# 086-005.net
KiCad netlist of a schematic drawn in EAGLE
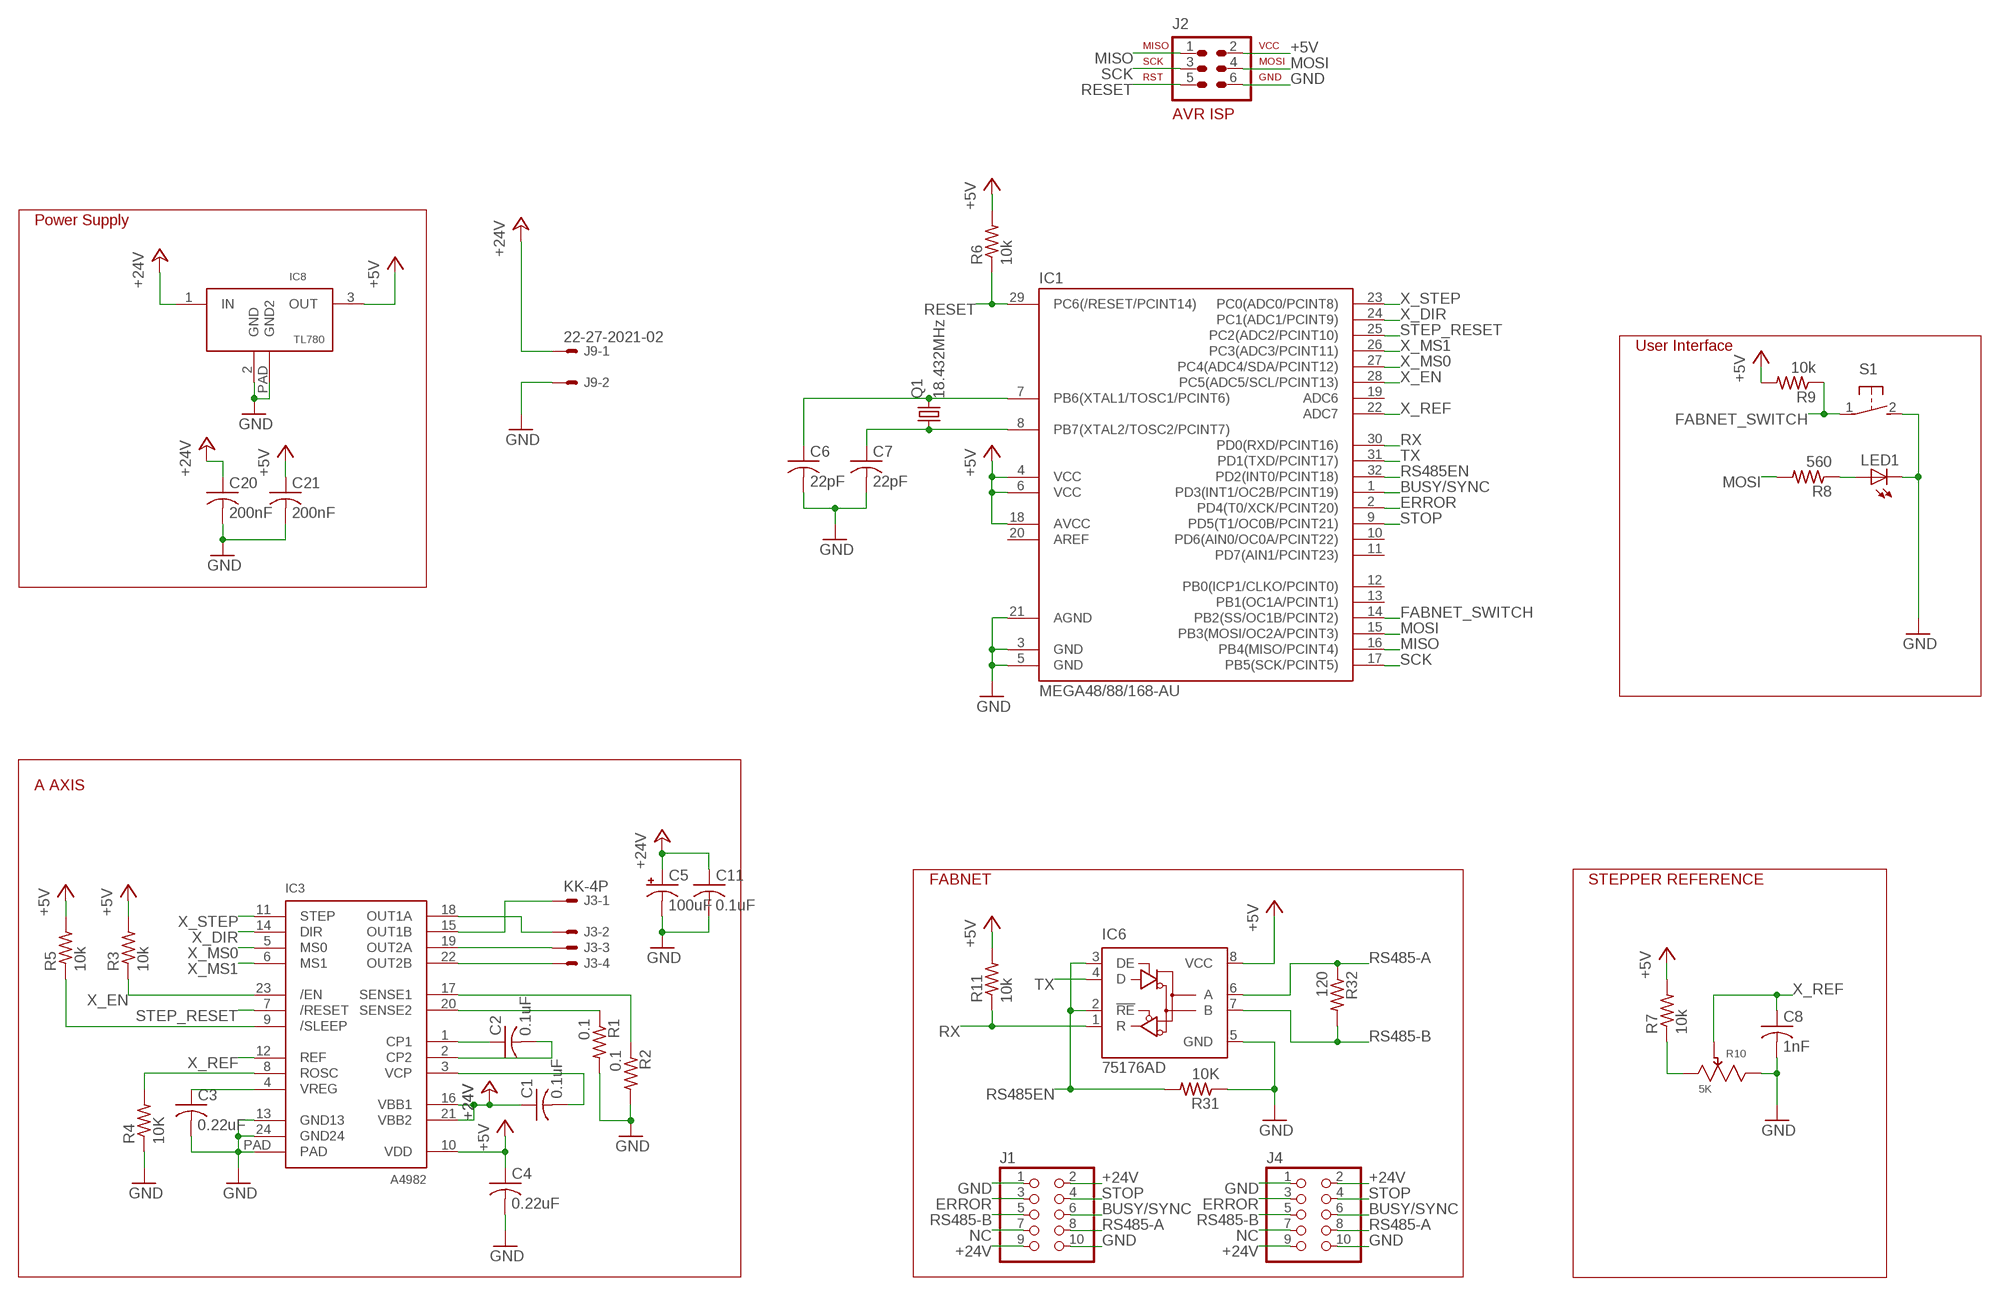
[diagram p0: schematic, sheet 1]

(export (version "E")
  (design (tool "Eeschema 10.0.6"))
  (components
    (comp (ref "C1")
      (value "0.1uF")
      (footprint "eagle-import:C0805")
      (libsource (lib "eagle-import") (part "C-USC0805"))
    )
    (comp (ref "C2")
      (value "0.1uF")
      (footprint "eagle-import:C0805")
      (libsource (lib "eagle-import") (part "C-USC0805"))
    )
    (comp (ref "C3")
      (value "0.22uF")
      (footprint "eagle-import:C0805")
      (libsource (lib "eagle-import") (part "C-USC0805"))
    )
    (comp (ref "C4")
      (value "0.22uF")
      (footprint "eagle-import:C0805")
      (libsource (lib "eagle-import") (part "C-USC0805"))
    )
    (comp (ref "C5")
      (value "100uF")
      (footprint "eagle-import:PANASONIC_D")
      (libsource (lib "eagle-import") (part "CPOL-USD"))
    )
    (comp (ref "C6")
      (value "22pF")
      (footprint "eagle-import:C0805")
      (libsource (lib "eagle-import") (part "C-USC0805"))
    )
    (comp (ref "C7")
      (value "22pF")
      (footprint "eagle-import:C0805")
      (libsource (lib "eagle-import") (part "C-USC0805"))
    )
    (comp (ref "C8")
      (value "1nF")
      (footprint "eagle-import:C0805")
      (libsource (lib "eagle-import") (part "C-USC0805"))
    )
    (comp (ref "C11")
      (value "0.1uF")
      (footprint "eagle-import:C0805")
      (libsource (lib "eagle-import") (part "C-USC0805"))
    )
    (comp (ref "C20")
      (value "200nF")
      (footprint "eagle-import:C0805")
      (libsource (lib "eagle-import") (part "C-USC0805"))
    )
    (comp (ref "C21")
      (value "200nF")
      (footprint "eagle-import:C0805")
      (libsource (lib "eagle-import") (part "C-USC0805"))
    )
    (comp (ref "IC1")
      (value "MEGA48/88/168-AU")
      (footprint "eagle-import:TQFP32-08")
      (libsource (lib "eagle-import") (part "MEGA48/88/168-AU"))
    )
    (comp (ref "IC3")
      (value "A4982")
      (footprint "eagle-import:TSSOP24_LP")
      (libsource (lib "eagle-import") (part "A4982"))
    )
    (comp (ref "IC6")
      (value "75176AD")
      (footprint "eagle-import:D_R-PDSO-G8")
      (libsource (lib "eagle-import") (part "75176AD"))
    )
    (comp (ref "IC8")
      (value "TL780_VREG")
      (footprint "eagle-import:D2PAK-3")
      (libsource (lib "eagle-import") (part "TL780_VREG"))
    )
    (comp (ref "J1")
      (value "PINHD-2X5")
      (footprint "eagle-import:2X05")
      (libsource (lib "eagle-import") (part "PINHD-2X5"))
    )
    (comp (ref "J2")
      (value "AVR-ISP-6VERT")
      (footprint "eagle-import:AVR-ISP-6")
      (libsource (lib "eagle-import") (part "AVR-ISP-6VERT"))
    )
    (comp (ref "J3")
      (value "KK-4P")
      (footprint "eagle-import:7395-04")
      (libsource (lib "eagle-import") (part "22-?-0405-7048"))
    )
    (comp (ref "J4")
      (value "PINHD-2X5")
      (footprint "eagle-import:2X05")
      (libsource (lib "eagle-import") (part "PINHD-2X5"))
    )
    (comp (ref "J9")
      (value "22-27-2021-02")
      (footprint "eagle-import:6410-02")
      (libsource (lib "eagle-import") (part "22-?-0227-2021"))
    )
    (comp (ref "LED1")
      (value "LEDCHIPLED_0603")
      (footprint "eagle-import:CHIPLED_0603")
      (libsource (lib "eagle-import") (part "LEDCHIPLED_0603"))
    )
    (comp (ref "Q1")
      (value "18.432MHz")
      (footprint "eagle-import:HC49UP")
      (fields (field (name "OC_FARNELL") "unknown") (field (name "OC_NEWARK") "unknown"))
      (libsource (lib "eagle-import") (part "CRYSTALHC49UP"))
    )
    (comp (ref "R1")
      (value "0.1")
      (footprint "eagle-import:R1206")
      (libsource (lib "eagle-import") (part "R-US_R1206"))
    )
    (comp (ref "R2")
      (value "0.1")
      (footprint "eagle-import:R1206")
      (libsource (lib "eagle-import") (part "R-US_R1206"))
    )
    (comp (ref "R3")
      (value "10k")
      (footprint "eagle-import:R0805")
      (libsource (lib "eagle-import") (part "R-US_R0805"))
    )
    (comp (ref "R4")
      (value "10K")
      (footprint "eagle-import:R0805")
      (libsource (lib "eagle-import") (part "R-US_R0805"))
    )
    (comp (ref "R5")
      (value "10k")
      (footprint "eagle-import:R0805")
      (libsource (lib "eagle-import") (part "R-US_R0805"))
    )
    (comp (ref "R6")
      (value "10k")
      (footprint "eagle-import:R0805")
      (libsource (lib "eagle-import") (part "R-US_R0805"))
    )
    (comp (ref "R7")
      (value "10k")
      (footprint "eagle-import:R0805")
      (libsource (lib "eagle-import") (part "R-US_R0805"))
    )
    (comp (ref "R8")
      (value "560")
      (footprint "eagle-import:R0805")
      (libsource (lib "eagle-import") (part "R-US_R0805"))
    )
    (comp (ref "R9")
      (value "10k")
      (footprint "eagle-import:R0805")
      (libsource (lib "eagle-import") (part "R-US_R0805"))
    )
    (comp (ref "R10")
      (value "5K")
      (footprint "eagle-import:BOURN_TRIM")
      (libsource (lib "eagle-import") (part "BOURN_POT"))
    )
    (comp (ref "R11")
      (value "10k")
      (footprint "eagle-import:R0805")
      (libsource (lib "eagle-import") (part "R-US_R0805"))
    )
    (comp (ref "R31")
      (value "10K")
      (footprint "eagle-import:R0805")
      (libsource (lib "eagle-import") (part "R-US_R0805"))
    )
    (comp (ref "R32")
      (value "120")
      (footprint "eagle-import:R0805")
      (libsource (lib "eagle-import") (part "R-US_R0805"))
    )
    (comp (ref "S1")
      (value "31-XX")
      (footprint "eagle-import:B3F-31XX")
      (fields (field (name "MPN") "B3F-3100"))
      (libsource (lib "eagle-import") (part "31-XX"))
    )
  )
  (nets
    (net (code "1") (name "+5V") (class "Default")
      (node (ref "C21") (pin "1") (pinfunction "1_1") (pintype "passive"))
      (node (ref "C4") (pin "1") (pinfunction "1_1") (pintype "passive"))
      (node (ref "IC1") (pin "18") (pinfunction "AVCC_18") (pintype "passive"))
      (node (ref "IC1") (pin "4") (pinfunction "VCC_4") (pintype "power_in"))
      (node (ref "IC1") (pin "6") (pinfunction "VCC_6") (pintype "power_in"))
      (node (ref "IC3") (pin "10") (pinfunction "VDD_10") (pintype "bidirectional"))
      (node (ref "IC6") (pin "8") (pinfunction "VCC_8") (pintype "power_in"))
      (node (ref "IC8") (pin "3") (pinfunction "OUT_3") (pintype "bidirectional"))
      (node (ref "J2") (pin "2") (pinfunction "2_2") (pintype "passive"))
      (node (ref "R11") (pin "2") (pinfunction "2_2") (pintype "passive"))
      (node (ref "R3") (pin "2") (pinfunction "2_2") (pintype "passive"))
      (node (ref "R5") (pin "2") (pinfunction "2_2") (pintype "passive"))
      (node (ref "R6") (pin "2") (pinfunction "2_2") (pintype "passive"))
      (node (ref "R7") (pin "2") (pinfunction "2_2") (pintype "passive"))
      (node (ref "R9") (pin "2") (pinfunction "2_2") (pintype "passive"))
    )
    (net (code "2") (name "+24V") (class "Default")
      (node (ref "C1") (pin "1") (pinfunction "1_1") (pintype "passive"))
      (node (ref "C11") (pin "1") (pinfunction "1_1") (pintype "passive"))
      (node (ref "C20") (pin "1") (pinfunction "1_1") (pintype "passive"))
      (node (ref "C5") (pin "+") (pinfunction "+_+") (pintype "passive"))
      (node (ref "IC3") (pin "16") (pinfunction "VBB1_16") (pintype "bidirectional"))
      (node (ref "IC3") (pin "21") (pinfunction "VBB2_21") (pintype "bidirectional"))
      (node (ref "IC8") (pin "1") (pinfunction "IN_1") (pintype "bidirectional"))
      (node (ref "J1") (pin "2") (pinfunction "2_2") (pintype "passive"))
      (node (ref "J1") (pin "9") (pinfunction "9_9") (pintype "passive"))
      (node (ref "J4") (pin "2") (pinfunction "2_2") (pintype "passive"))
      (node (ref "J4") (pin "9") (pinfunction "9_9") (pintype "passive"))
      (node (ref "J9") (pin "1") (pinfunction "S_1") (pintype "passive"))
    )
    (net (code "3") (name "/BUSY{slash}SYNC") (class "Default")
      (node (ref "IC1") (pin "1") (pinfunction "PD3(INT1/OC2B/PCINT19)_1") (pintype "bidirectional"))
      (node (ref "J1") (pin "6") (pinfunction "6_6") (pintype "passive"))
      (node (ref "J4") (pin "6") (pinfunction "6_6") (pintype "passive"))
    )
    (net (code "4") (name "/ERROR") (class "Default")
      (node (ref "IC1") (pin "2") (pinfunction "PD4(T0/XCK/PCINT20)_2") (pintype "bidirectional"))
      (node (ref "J1") (pin "3") (pinfunction "3_3") (pintype "passive"))
      (node (ref "J4") (pin "3") (pinfunction "3_3") (pintype "passive"))
    )
    (net (code "5") (name "/FABNET_SWITCH") (class "Default")
      (node (ref "IC1") (pin "14") (pinfunction "PB2(SS/OC1B/PCINT2)_14") (pintype "bidirectional"))
      (node (ref "R9") (pin "1") (pinfunction "1_1") (pintype "passive"))
      (node (ref "S1") (pin "1") (pinfunction "P_1") (pintype "passive"))
    )
    (net (code "6") (name "/MISO") (class "Default")
      (node (ref "IC1") (pin "16") (pinfunction "PB4(MISO/PCINT4)_16") (pintype "bidirectional"))
      (node (ref "J2") (pin "1") (pinfunction "1_1") (pintype "passive"))
    )
    (net (code "7") (name "/MOSI") (class "Default")
      (node (ref "IC1") (pin "15") (pinfunction "PB3(MOSI/OC2A/PCINT3)_15") (pintype "bidirectional"))
      (node (ref "J2") (pin "4") (pinfunction "4_4") (pintype "passive"))
      (node (ref "R8") (pin "2") (pinfunction "2_2") (pintype "passive"))
    )
    (net (code "8") (name "/NC") (class "Default")
      (node (ref "J1") (pin "7") (pinfunction "7_7") (pintype "passive"))
      (node (ref "J4") (pin "7") (pinfunction "7_7") (pintype "passive"))
    )
    (net (code "9") (name "/RESET") (class "Default")
      (node (ref "IC1") (pin "29") (pinfunction "PC6(/RESET/PCINT14)_29") (pintype "bidirectional"))
      (node (ref "J2") (pin "5") (pinfunction "5_5") (pintype "passive"))
      (node (ref "R6") (pin "1") (pinfunction "1_1") (pintype "passive"))
    )
    (net (code "10") (name "/RS485-A") (class "Default")
      (node (ref "IC6") (pin "6") (pinfunction "A_6") (pintype "output"))
      (node (ref "J1") (pin "8") (pinfunction "8_8") (pintype "passive"))
      (node (ref "J4") (pin "8") (pinfunction "8_8") (pintype "passive"))
      (node (ref "R32") (pin "1") (pinfunction "1_1") (pintype "passive"))
    )
    (net (code "11") (name "/RS485-B") (class "Default")
      (node (ref "IC6") (pin "7") (pinfunction "B_7") (pintype "output"))
      (node (ref "J1") (pin "5") (pinfunction "5_5") (pintype "passive"))
      (node (ref "J4") (pin "5") (pinfunction "5_5") (pintype "passive"))
      (node (ref "R32") (pin "2") (pinfunction "2_2") (pintype "passive"))
    )
    (net (code "12") (name "/RS485EN") (class "Default")
      (node (ref "IC1") (pin "32") (pinfunction "PD2(INT0/PCINT18)_32") (pintype "bidirectional"))
      (node (ref "IC6") (pin "2") (pinfunction "~{RE}_2") (pintype "input"))
      (node (ref "IC6") (pin "3") (pinfunction "DE_3") (pintype "input"))
      (node (ref "R31") (pin "2") (pinfunction "2_2") (pintype "passive"))
    )
    (net (code "13") (name "/RX") (class "Default")
      (node (ref "IC1") (pin "30") (pinfunction "PD0(RXD/PCINT16)_30") (pintype "bidirectional"))
      (node (ref "IC6") (pin "1") (pinfunction "R_1") (pintype "input"))
      (node (ref "R11") (pin "1") (pinfunction "1_1") (pintype "passive"))
    )
    (net (code "14") (name "/SCK") (class "Default")
      (node (ref "IC1") (pin "17") (pinfunction "PB5(SCK/PCINT5)_17") (pintype "bidirectional"))
      (node (ref "J2") (pin "3") (pinfunction "3_3") (pintype "passive"))
    )
    (net (code "15") (name "/STEP_RESET") (class "Default")
      (node (ref "IC1") (pin "25") (pinfunction "PC2(ADC2/PCINT10)_25") (pintype "bidirectional"))
      (node (ref "IC3") (pin "7") (pinfunction "/RESET_7") (pintype "bidirectional"))
    )
    (net (code "16") (name "/STOP") (class "Default")
      (node (ref "IC1") (pin "9") (pinfunction "PD5(T1/OC0B/PCINT21)_9") (pintype "bidirectional"))
      (node (ref "J1") (pin "4") (pinfunction "4_4") (pintype "passive"))
      (node (ref "J4") (pin "4") (pinfunction "4_4") (pintype "passive"))
    )
    (net (code "17") (name "/TX") (class "Default")
      (node (ref "IC1") (pin "31") (pinfunction "PD1(TXD/PCINT17)_31") (pintype "bidirectional"))
      (node (ref "IC6") (pin "4") (pinfunction "D_4") (pintype "input"))
    )
    (net (code "18") (name "/X_DIR") (class "Default")
      (node (ref "IC1") (pin "24") (pinfunction "PC1(ADC1/PCINT9)_24") (pintype "bidirectional"))
      (node (ref "IC3") (pin "14") (pinfunction "DIR_14") (pintype "bidirectional"))
    )
    (net (code "19") (name "/X_EN") (class "Default")
      (node (ref "IC1") (pin "28") (pinfunction "PC5(ADC5/SCL/PCINT13)_28") (pintype "bidirectional"))
      (node (ref "IC3") (pin "23") (pinfunction "/EN_23") (pintype "bidirectional"))
      (node (ref "R3") (pin "1") (pinfunction "1_1") (pintype "passive"))
    )
    (net (code "20") (name "/X_MS0") (class "Default")
      (node (ref "IC1") (pin "27") (pinfunction "PC4(ADC4/SDA/PCINT12)_27") (pintype "bidirectional"))
      (node (ref "IC3") (pin "5") (pinfunction "MS0_5") (pintype "bidirectional"))
    )
    (net (code "21") (name "/X_MS1") (class "Default")
      (node (ref "IC1") (pin "26") (pinfunction "PC3(ADC3/PCINT11)_26") (pintype "bidirectional"))
      (node (ref "IC3") (pin "6") (pinfunction "MS1_6") (pintype "bidirectional"))
    )
    (net (code "22") (name "/X_REF") (class "Default")
      (node (ref "C8") (pin "1") (pinfunction "1_1") (pintype "passive"))
      (node (ref "IC1") (pin "22") (pinfunction "ADC7_22") (pintype "passive"))
      (node (ref "IC3") (pin "12") (pinfunction "REF_12") (pintype "bidirectional"))
      (node (ref "R10") (pin "2") (pinfunction "2_2") (pintype "bidirectional"))
    )
    (net (code "23") (name "/X_STEP") (class "Default")
      (node (ref "IC1") (pin "23") (pinfunction "PC0(ADC0/PCINT8)_23") (pintype "bidirectional"))
      (node (ref "IC3") (pin "11") (pinfunction "STEP_11") (pintype "bidirectional"))
    )
    (net (code "24") (name "GND") (class "Default")
      (node (ref "C11") (pin "2") (pinfunction "2_2") (pintype "passive"))
      (node (ref "C20") (pin "2") (pinfunction "2_2") (pintype "passive"))
      (node (ref "C21") (pin "2") (pinfunction "2_2") (pintype "passive"))
      (node (ref "C3") (pin "2") (pinfunction "2_2") (pintype "passive"))
      (node (ref "C4") (pin "2") (pinfunction "2_2") (pintype "passive"))
      (node (ref "C5") (pin "-") (pinfunction "-_-") (pintype "passive"))
      (node (ref "C6") (pin "2") (pinfunction "2_2") (pintype "passive"))
      (node (ref "C7") (pin "2") (pinfunction "2_2") (pintype "passive"))
      (node (ref "C8") (pin "2") (pinfunction "2_2") (pintype "passive"))
      (node (ref "IC1") (pin "21") (pinfunction "AGND_21") (pintype "power_in"))
      (node (ref "IC1") (pin "3") (pinfunction "GND_3") (pintype "power_in"))
      (node (ref "IC1") (pin "5") (pinfunction "GND_5") (pintype "power_in"))
      (node (ref "IC3") (pin "13") (pinfunction "GND13_13") (pintype "bidirectional"))
      (node (ref "IC3") (pin "24") (pinfunction "GND24_24") (pintype "bidirectional"))
      (node (ref "IC3") (pin "PAD") (pinfunction "PAD_PAD") (pintype "bidirectional"))
      (node (ref "IC6") (pin "5") (pinfunction "GND_5") (pintype "power_in"))
      (node (ref "IC8") (pin "2") (pinfunction "GND_2") (pintype "bidirectional"))
      (node (ref "IC8") (pin "PAD") (pinfunction "GND2_PAD") (pintype "bidirectional"))
      (node (ref "J1") (pin "1") (pinfunction "1_1") (pintype "passive"))
      (node (ref "J1") (pin "10") (pinfunction "10_10") (pintype "passive"))
      (node (ref "J2") (pin "6") (pinfunction "6_6") (pintype "passive"))
      (node (ref "J4") (pin "1") (pinfunction "1_1") (pintype "passive"))
      (node (ref "J4") (pin "10") (pinfunction "10_10") (pintype "passive"))
      (node (ref "J9") (pin "2") (pinfunction "S_2") (pintype "passive"))
      (node (ref "LED1") (pin "C") (pinfunction "C_C") (pintype "passive"))
      (node (ref "R1") (pin "2") (pinfunction "2_2") (pintype "passive"))
      (node (ref "R10") (pin "3") (pinfunction "3_3") (pintype "bidirectional"))
      (node (ref "R2") (pin "2") (pinfunction "2_2") (pintype "passive"))
      (node (ref "R31") (pin "1") (pinfunction "1_1") (pintype "passive"))
      (node (ref "R4") (pin "1") (pinfunction "1_1") (pintype "passive"))
      (node (ref "S1") (pin "2") (pinfunction "S_2") (pintype "passive"))
    )
    (net (code "25") (name "Net-(IC1-PB6(XTAL1{slash}TOSC1{slash}PCINT6))") (class "Default")
      (node (ref "C6") (pin "1") (pinfunction "1_1") (pintype "passive"))
      (node (ref "IC1") (pin "7") (pinfunction "PB6(XTAL1/TOSC1/PCINT6)_7") (pintype "bidirectional"))
      (node (ref "Q1") (pin "2") (pinfunction "2_2") (pintype "passive"))
    )
    (net (code "26") (name "Net-(IC1-PB7(XTAL2{slash}TOSC2{slash}PCINT7))") (class "Default")
      (node (ref "C7") (pin "1") (pinfunction "1_1") (pintype "passive"))
      (node (ref "IC1") (pin "8") (pinfunction "PB7(XTAL2/TOSC2/PCINT7)_8") (pintype "bidirectional"))
      (node (ref "Q1") (pin "1") (pinfunction "1_1") (pintype "passive"))
    )
    (net (code "27") (name "Net-(IC3-CP1)") (class "Default")
      (node (ref "C2") (pin "1") (pinfunction "1_1") (pintype "passive"))
      (node (ref "IC3") (pin "1") (pinfunction "CP1_1") (pintype "bidirectional"))
    )
    (net (code "28") (name "Net-(IC3-CP2)") (class "Default")
      (node (ref "C2") (pin "2") (pinfunction "2_2") (pintype "passive"))
      (node (ref "IC3") (pin "2") (pinfunction "CP2_2") (pintype "bidirectional"))
    )
    (net (code "29") (name "Net-(IC3-OUT1A)") (class "Default")
      (node (ref "IC3") (pin "18") (pinfunction "OUT1A_18") (pintype "bidirectional"))
      (node (ref "J3") (pin "2") (pinfunction "S_2") (pintype "passive"))
    )
    (net (code "30") (name "Net-(IC3-OUT1B)") (class "Default")
      (node (ref "IC3") (pin "15") (pinfunction "OUT1B_15") (pintype "bidirectional"))
      (node (ref "J3") (pin "1") (pinfunction "S_1") (pintype "passive"))
    )
    (net (code "31") (name "Net-(IC3-OUT2A)") (class "Default")
      (node (ref "IC3") (pin "19") (pinfunction "OUT2A_19") (pintype "bidirectional"))
      (node (ref "J3") (pin "3") (pinfunction "S_3") (pintype "passive"))
    )
    (net (code "32") (name "Net-(IC3-OUT2B)") (class "Default")
      (node (ref "IC3") (pin "22") (pinfunction "OUT2B_22") (pintype "bidirectional"))
      (node (ref "J3") (pin "4") (pinfunction "S_4") (pintype "passive"))
    )
    (net (code "33") (name "Net-(IC3-ROSC)") (class "Default")
      (node (ref "IC3") (pin "8") (pinfunction "ROSC_8") (pintype "bidirectional"))
      (node (ref "R4") (pin "2") (pinfunction "2_2") (pintype "passive"))
    )
    (net (code "34") (name "Net-(IC3-SENSE1)") (class "Default")
      (node (ref "IC3") (pin "17") (pinfunction "SENSE1_17") (pintype "bidirectional"))
      (node (ref "R2") (pin "1") (pinfunction "1_1") (pintype "passive"))
    )
    (net (code "35") (name "Net-(IC3-SENSE2)") (class "Default")
      (node (ref "IC3") (pin "20") (pinfunction "SENSE2_20") (pintype "bidirectional"))
      (node (ref "R1") (pin "1") (pinfunction "1_1") (pintype "passive"))
    )
    (net (code "36") (name "Net-(IC3-VCP)") (class "Default")
      (node (ref "C1") (pin "2") (pinfunction "2_2") (pintype "passive"))
      (node (ref "IC3") (pin "3") (pinfunction "VCP_3") (pintype "bidirectional"))
    )
    (net (code "37") (name "Net-(IC3-VREG)") (class "Default")
      (node (ref "C3") (pin "1") (pinfunction "1_1") (pintype "passive"))
      (node (ref "IC3") (pin "4") (pinfunction "VREG_4") (pintype "bidirectional"))
    )
    (net (code "38") (name "Net-(IC3-{slash}SLEEP)") (class "Default")
      (node (ref "IC3") (pin "9") (pinfunction "/SLEEP_9") (pintype "bidirectional"))
      (node (ref "R5") (pin "1") (pinfunction "1_1") (pintype "passive"))
    )
    (net (code "39") (name "Net-(LED1-PadA)") (class "Default")
      (node (ref "LED1") (pin "A") (pinfunction "A_A") (pintype "passive"))
      (node (ref "R8") (pin "1") (pinfunction "1_1") (pintype "passive"))
    )
    (net (code "40") (name "Net-(R10-Pad1)") (class "Default")
      (node (ref "R10") (pin "1") (pinfunction "1_1") (pintype "bidirectional"))
      (node (ref "R7") (pin "1") (pinfunction "1_1") (pintype "passive"))
    )
    (net (code "41") (name "unconnected-(IC1-ADC6-Pad19)") (class "Default")
      (node (ref "IC1") (pin "19") (pinfunction "ADC6_19") (pintype "passive"))
    )
    (net (code "42") (name "unconnected-(IC1-AREF-Pad20)") (class "Default")
      (node (ref "IC1") (pin "20") (pinfunction "AREF_20") (pintype "passive"))
    )
    (net (code "43") (name "unconnected-(IC1-PB0(ICP1{slash}CLKO{slash}PCINT0)-Pad12)") (class "Default")
      (node (ref "IC1") (pin "12") (pinfunction "PB0(ICP1/CLKO/PCINT0)_12") (pintype "bidirectional"))
    )
    (net (code "44") (name "unconnected-(IC1-PB1(OC1A{slash}PCINT1)-Pad13)") (class "Default")
      (node (ref "IC1") (pin "13") (pinfunction "PB1(OC1A/PCINT1)_13") (pintype "bidirectional"))
    )
    (net (code "45") (name "unconnected-(IC1-PD6(AIN0{slash}OC0A{slash}PCINT22)-Pad10)") (class "Default")
      (node (ref "IC1") (pin "10") (pinfunction "PD6(AIN0/OC0A/PCINT22)_10") (pintype "bidirectional"))
    )
    (net (code "46") (name "unconnected-(IC1-PD7(AIN1{slash}PCINT23)-Pad11)") (class "Default")
      (node (ref "IC1") (pin "11") (pinfunction "PD7(AIN1/PCINT23)_11") (pintype "bidirectional"))
    )
  )
)
